# gate_board_v1.net
KiCad netlist of a schematic drawn in EAGLE
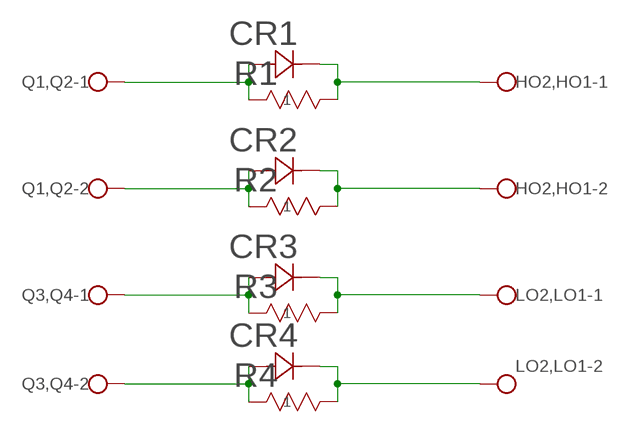
[diagram p0: schematic, sheet 1]

(export (version "E")
  (design (tool "Eeschema 10.0.6"))
  (components
    (comp (ref "CR1")
      (value "1N4007CR_1N4005_ONS")
      (footprint "eagle-import:CR_1N4005_ONS")
      (fields
        (field (name "MANUFACTURER_PART_NUMBER") "1N4007")
        (field (name "COPYRIGHT") "Copyright (C) 2024 Ultra Librarian. All rights reserved.")
      )
      (libsource (lib "eagle-import") (part "1N4007CR_1N4005_ONS"))
    )
    (comp (ref "CR2")
      (value "1N4007CR_1N4005_ONS")
      (footprint "eagle-import:CR_1N4005_ONS")
      (fields
        (field (name "MANUFACTURER_PART_NUMBER") "1N4007")
        (field (name "COPYRIGHT") "Copyright (C) 2024 Ultra Librarian. All rights reserved.")
      )
      (libsource (lib "eagle-import") (part "1N4007CR_1N4005_ONS"))
    )
    (comp (ref "CR3")
      (value "1N4007CR_1N4005_ONS")
      (footprint "eagle-import:CR_1N4005_ONS")
      (fields
        (field (name "MANUFACTURER_PART_NUMBER") "1N4007")
        (field (name "COPYRIGHT") "Copyright (C) 2024 Ultra Librarian. All rights reserved.")
      )
      (libsource (lib "eagle-import") (part "1N4007CR_1N4005_ONS"))
    )
    (comp (ref "CR4")
      (value "1N4007CR_1N4005_ONS")
      (footprint "eagle-import:CR_1N4005_ONS")
      (fields
        (field (name "MANUFACTURER_PART_NUMBER") "1N4007")
        (field (name "COPYRIGHT") "Copyright (C) 2024 Ultra Librarian. All rights reserved.")
      )
      (libsource (lib "eagle-import") (part "1N4007CR_1N4005_ONS"))
    )
    (comp (ref "HO2,HO1")
      (value "W237-02P")
      (footprint "eagle-import:W237-132")
      (libsource (lib "eagle-import") (part "W237-02P"))
    )
    (comp (ref "LO2,LO1")
      (value "W237-02P")
      (footprint "eagle-import:W237-132")
      (libsource (lib "eagle-import") (part "W237-02P"))
    )
    (comp (ref "Q1,Q2")
      (value "W237-02P")
      (footprint "eagle-import:W237-132")
      (libsource (lib "eagle-import") (part "W237-02P"))
    )
    (comp (ref "Q3,Q4")
      (value "W237-02P")
      (footprint "eagle-import:W237-132")
      (libsource (lib "eagle-import") (part "W237-02P"))
    )
    (comp (ref "R1")
      (value "CF14JT10K0STA_CF14_STP")
      (footprint "eagle-import:STA_CF14_STP")
      (fields
        (field (name "MANUFACTURER_PART_NUMBER") "CF14JT10K0")
        (field (name "COPYRIGHT") "Copyright (C) 2024 Ultra Librarian. All rights reserved.")
      )
      (libsource (lib "eagle-import") (part "CF14JT10K0STA_CF14_STP"))
    )
    (comp (ref "R2")
      (value "CF14JT10K0STA_CF14_STP")
      (footprint "eagle-import:STA_CF14_STP")
      (fields
        (field (name "MANUFACTURER_PART_NUMBER") "CF14JT10K0")
        (field (name "COPYRIGHT") "Copyright (C) 2024 Ultra Librarian. All rights reserved.")
      )
      (libsource (lib "eagle-import") (part "CF14JT10K0STA_CF14_STP"))
    )
    (comp (ref "R3")
      (value "CF14JT10K0STA_CF14_STP")
      (footprint "eagle-import:STA_CF14_STP")
      (fields
        (field (name "MANUFACTURER_PART_NUMBER") "CF14JT10K0")
        (field (name "COPYRIGHT") "Copyright (C) 2024 Ultra Librarian. All rights reserved.")
      )
      (libsource (lib "eagle-import") (part "CF14JT10K0STA_CF14_STP"))
    )
    (comp (ref "R4")
      (value "CF14JT10K0STA_CF14_STP")
      (footprint "eagle-import:STA_CF14_STP")
      (fields
        (field (name "MANUFACTURER_PART_NUMBER") "CF14JT10K0")
        (field (name "COPYRIGHT") "Copyright (C) 2024 Ultra Librarian. All rights reserved.")
      )
      (libsource (lib "eagle-import") (part "CF14JT10K0STA_CF14_STP"))
    )
  )
  (nets
    (net (code "1") (name "Net-(HO2,HO1A-KL)") (class "Default")
      (node (ref "CR1") (pin "1") (pinfunction "1_1") (pintype "passive"))
      (node (ref "HO2,HO1") (pin "1") (pinfunction "KL_1") (pintype "passive"))
      (node (ref "R1") (pin "2") (pinfunction "2_2") (pintype "passive"))
    )
    (net (code "2") (name "Net-(HO2,HO1B-KL)") (class "Default")
      (node (ref "CR2") (pin "1") (pinfunction "1_1") (pintype "passive"))
      (node (ref "HO2,HO1") (pin "2") (pinfunction "KL_2") (pintype "passive"))
      (node (ref "R2") (pin "2") (pinfunction "2_2") (pintype "passive"))
    )
    (net (code "3") (name "Net-(LO2,LO1A-KL)") (class "Default")
      (node (ref "CR3") (pin "1") (pinfunction "1_1") (pintype "passive"))
      (node (ref "LO2,LO1") (pin "1") (pinfunction "KL_1") (pintype "passive"))
      (node (ref "R3") (pin "2") (pinfunction "2_2") (pintype "passive"))
    )
    (net (code "4") (name "Net-(LO2,LO1B-KL)") (class "Default")
      (node (ref "CR4") (pin "1") (pinfunction "1_1") (pintype "passive"))
      (node (ref "LO2,LO1") (pin "2") (pinfunction "KL_2") (pintype "passive"))
      (node (ref "R4") (pin "2") (pinfunction "2_2") (pintype "passive"))
    )
    (net (code "5") (name "Net-(Q1,Q2A-KL)") (class "Default")
      (node (ref "CR1") (pin "2") (pinfunction "2_2") (pintype "passive"))
      (node (ref "Q1,Q2") (pin "1") (pinfunction "KL_1") (pintype "passive"))
      (node (ref "R1") (pin "1") (pinfunction "1_1") (pintype "passive"))
    )
    (net (code "6") (name "Net-(Q1,Q2B-KL)") (class "Default")
      (node (ref "CR2") (pin "2") (pinfunction "2_2") (pintype "passive"))
      (node (ref "Q1,Q2") (pin "2") (pinfunction "KL_2") (pintype "passive"))
      (node (ref "R2") (pin "1") (pinfunction "1_1") (pintype "passive"))
    )
    (net (code "7") (name "Net-(Q3,Q4A-KL)") (class "Default")
      (node (ref "CR3") (pin "2") (pinfunction "2_2") (pintype "passive"))
      (node (ref "Q3,Q4") (pin "1") (pinfunction "KL_1") (pintype "passive"))
      (node (ref "R3") (pin "1") (pinfunction "1_1") (pintype "passive"))
    )
    (net (code "8") (name "Net-(Q3,Q4B-KL)") (class "Default")
      (node (ref "CR4") (pin "2") (pinfunction "2_2") (pintype "passive"))
      (node (ref "Q3,Q4") (pin "2") (pinfunction "KL_2") (pintype "passive"))
      (node (ref "R4") (pin "1") (pinfunction "1_1") (pintype "passive"))
    )
  )
)
